# Laser_protection.net
KiCad netlist of a schematic drawn in Altium Designer
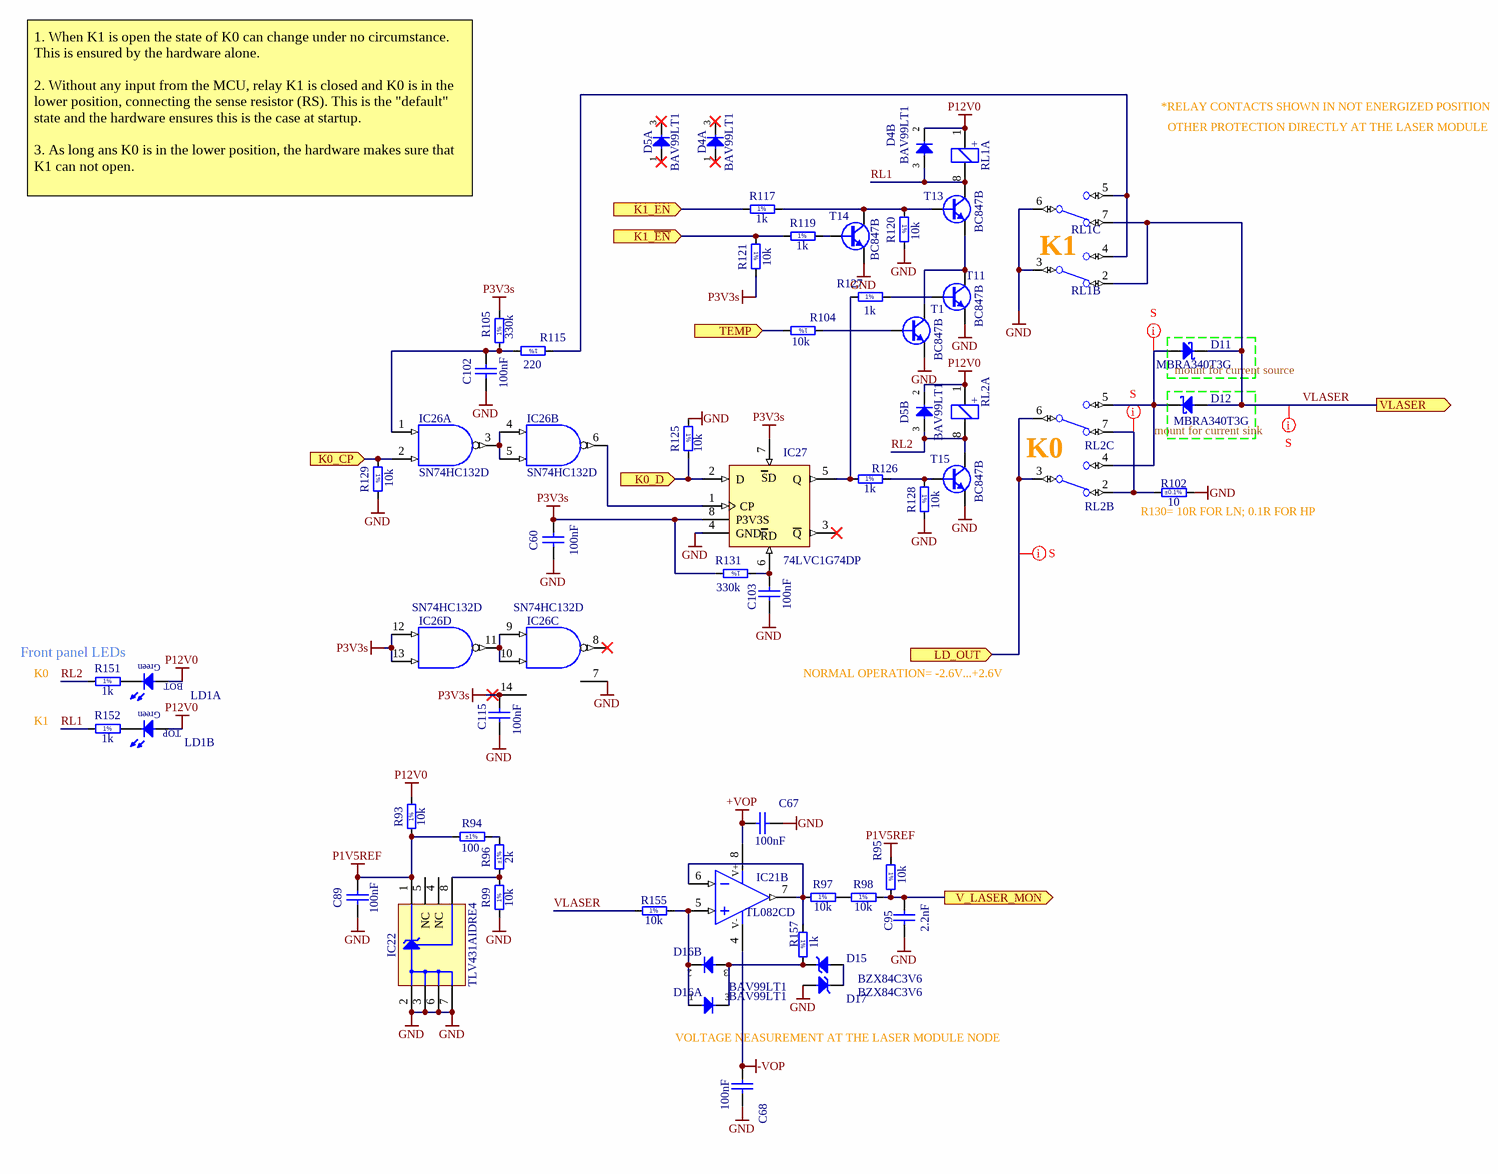
[diagram p0: Laser protection.SchDoc]

(export (version "E")
  (design (tool "Eeschema 10.0.6"))
  (components
    (comp (ref "C60")
      (value "100nF")
      (footprint "CAPC1608X87N")
      (description "Non-polarised capacitor")
      (fields
        (field (name "PART NUMBER") "CC0603_100NF_50V_10%_X7R")
        (field (name "VOLTAGE") "50V")
        (field (name "AUTHOR") "CERN DEM JLC")
      )
      (libsource (lib "Capacitors") (part "Capacitor - non polarized"))
    )
    (comp (ref "C67")
      (value "100nF")
      (footprint "CAPC1608X87N")
      (description "Non-polarised capacitor")
      (fields
        (field (name "PART NUMBER") "CC0603_100NF_50V_10%_X7R")
        (field (name "VOLTAGE") "50V")
        (field (name "AUTHOR") "CERN DEM JLC")
      )
      (libsource (lib "Capacitors") (part "Capacitor - non polarized"))
    )
    (comp (ref "C68")
      (value "100nF")
      (footprint "CAPC1608X87N")
      (description "Non-polarised capacitor")
      (fields
        (field (name "PART NUMBER") "CC0603_100NF_50V_10%_X7R")
        (field (name "VOLTAGE") "50V")
        (field (name "AUTHOR") "CERN DEM JLC")
      )
      (libsource (lib "Capacitors") (part "Capacitor - non polarized"))
    )
    (comp (ref "C89")
      (value "100nF")
      (footprint "CAPC1608X87N")
      (description "Non-polarised capacitor")
      (fields
        (field (name "PART NUMBER") "CC0603_100NF_50V_10%_X7R")
        (field (name "VOLTAGE") "50V")
        (field (name "AUTHOR") "CERN DEM JLC")
      )
      (libsource (lib "Capacitors") (part "Capacitor - non polarized"))
    )
    (comp (ref "C95")
      (value "2.2nF")
      (footprint "CAPC1608X87N")
      (description "Non-polarised capacitor")
      (fields
        (field (name "PART NUMBER") "CC0603_2.2NF_50V_5%_C0G")
        (field (name "VOLTAGE") "50V")
        (field (name "AUTHOR") "CERN DEM JMW")
      )
      (libsource (lib "Capacitors") (part "Capacitor - non polarized"))
    )
    (comp (ref "C102")
      (value "100nF")
      (footprint "CAPC1608X87N")
      (description "Non-polarised capacitor")
      (fields
        (field (name "PART NUMBER") "CC0603_100NF_50V_10%_X7R")
        (field (name "VOLTAGE") "50V")
        (field (name "AUTHOR") "CERN DEM JLC")
      )
      (libsource (lib "Capacitors") (part "Capacitor - non polarized"))
    )
    (comp (ref "C103")
      (value "100nF")
      (footprint "CAPC1608X87N")
      (description "Non-polarised capacitor")
      (fields
        (field (name "PART NUMBER") "CC0603_100NF_50V_10%_X7R")
        (field (name "VOLTAGE") "50V")
        (field (name "AUTHOR") "CERN DEM JLC")
      )
      (libsource (lib "Capacitors") (part "Capacitor - non polarized"))
    )
    (comp (ref "C115")
      (value "100nF")
      (footprint "CAPC1608X87N")
      (description "Non-polarised capacitor")
      (fields
        (field (name "PART NUMBER") "CC0603_100NF_50V_10%_X7R")
        (field (name "VOLTAGE") "50V")
        (field (name "AUTHOR") "CERN DEM JLC")
      )
      (libsource (lib "Capacitors") (part "Capacitor - non polarized"))
    )
    (comp (ref "D4")
      (value "BAV99LT1")
      (footprint "SOT95P240X110-3N")
      (description "Serial Diode")
      (fields
        (field (name "VOLTAGE") "70V")
        (field (name "POWER") "225mW")
        (field (name "AUTHOR") "CERN DEM JLC")
      )
      (libsource (lib "ICs And Semiconductors") (part "Diode x2 A1C3_A3C2"))
    )
    (comp (ref "D5")
      (value "BAV99LT1")
      (footprint "SOT95P240X110-3N")
      (description "Serial Diode")
      (fields
        (field (name "VOLTAGE") "70V")
        (field (name "POWER") "225mW")
        (field (name "AUTHOR") "CERN DEM JLC")
      )
      (libsource (lib "ICs And Semiconductors") (part "Diode x2 A1C3_A3C2"))
    )
    (comp (ref "D11")
      (value "MBRA340T3G")
      (footprint "DIOM5226X220N")
      (description "Schottky Diode")
      (fields
        (field (name "VOLTAGE") "40V")
        (field (name "POWER") "3A")
        (field (name "AUTHOR") "CERN DEM JLC")
      )
      (libsource (lib "ICs And Semiconductors") (part "Diode Schottky"))
    )
    (comp (ref "D12")
      (value "MBRA340T3G")
      (footprint "DIOM5226X220N")
      (description "Schottky Diode")
      (fields
        (field (name "VOLTAGE") "40V")
        (field (name "POWER") "3A")
        (field (name "AUTHOR") "CERN DEM JLC")
      )
      (libsource (lib "ICs And Semiconductors") (part "Diode Schottky"))
    )
    (comp (ref "D15")
      (value "BZX84C3V6")
      (footprint "SOT95P240X130-3N")
      (description "Diode Zener Anode Pin 1 Cathode Pin 3 (Pas de pin 2)")
      (fields
        (field (name "VOLTAGE") "3V6")
        (field (name "POWER") "350mW")
        (field (name "AUTHOR") "CERN DEM JLC")
      )
      (libsource (lib "ICs And Semiconductors") (part "Diode Zener A1C3"))
    )
    (comp (ref "D16")
      (value "BAV99LT1")
      (footprint "SOT95P240X110-3N")
      (description "Serial Diode")
      (fields
        (field (name "VOLTAGE") "70V")
        (field (name "POWER") "225mW")
        (field (name "AUTHOR") "CERN DEM JLC")
      )
      (libsource (lib "ICs And Semiconductors") (part "Diode x2 A1C3_A3C2"))
    )
    (comp (ref "D17")
      (value "BZX84C3V6")
      (footprint "SOT95P240X130-3N")
      (description "Diode Zener Anode Pin 1 Cathode Pin 3 (Pas de pin 2)")
      (fields
        (field (name "VOLTAGE") "3V6")
        (field (name "POWER") "350mW")
        (field (name "AUTHOR") "CERN DEM JLC")
      )
      (libsource (lib "ICs And Semiconductors") (part "Diode Zener A1C3"))
    )
    (comp (ref "IC21")
      (value "TL082CD")
      (footprint "SOIC127P600X175-8N")
      (description "Dual Operational Amplifier")
      (fields (field (name "MANUFACTURER") "TEXAS INSTRUMENTS") (field (name "AUTHOR") "CERN DEM JLC"))
      (libsource (lib "ICs And Semiconductors") (part "Operational Amplifier x2 Type1"))
    )
    (comp (ref "IC22")
      (value "TLV431AIDRE4")
      (footprint "SOIC127P600X175-8N")
      (description "Precision Programmable Reference")
      (fields (field (name "MANUFACTURER") "TEXAS INSTRUMENTS") (field (name "AUTHOR") "CERN DEM JLC"))
      (libsource (lib "ICs And Semiconductors") (part "TL431xD"))
    )
    (comp (ref "IC26")
      (value "SN74HC132D")
      (footprint "SOIC127P600X175-14N")
      (description "Quad Positive NAND Gate With Schmitt-Trigger Input")
      (fields (field (name "MANUFACTURER") "TEXAS INSTRUMENTS") (field (name "AUTHOR") "CERN DEM JLC"))
      (libsource (lib "") (part "74132_1"))
    )
    (comp (ref "IC27")
      (value "74LVC1G74DP")
      (footprint "SOP65P400X110-8N")
      (description "Single D-type flip-flop with set and reset, positive edge trigger")
      (fields (field (name "MANUFACTURER") "NXP SEMICONDUCTORS") (field (name "AUTHOR") "CERN DEM JLC"))
      (libsource (lib "ICs And Semiconductors") (part "741G74"))
    )
    (comp (ref "LD1")
      (value "Green/Green")
      (footprint "LED_DIALIGHT_571-0122F")
      (description "LED x2 Green 1C2A-BOT_3C4A-TOP")
      (fields
        (field (name "PART NUMBER") "LED_DIALIGHT_571-0122F")
        (field (name "MANUFACTURER") "DIALIGHT")
        (field (name "AUTHOR") "CERN DEM JLC")
      )
      (libsource (lib "ICs And Semiconductors") (part "LED x2 Green 1C2A-BOT_3C4A-TOP"))
    )
    (comp (ref "R93")
      (value "10k")
      (footprint "RESC1608X55N")
      (description "Resistor - 1%")
      (fields
        (field (name "PART NUMBER") "R0603_10K_1%_0.1W_100PPM")
        (field (name "POWER") "0.1W")
        (field (name "AUTHOR") "CERN DEM JLC")
      )
      (libsource (lib "Resistors") (part "Resistor - 1%"))
    )
    (comp (ref "R94")
      (value "100")
      (footprint "RESC1608X55N")
      (description "Resistor - 1%")
      (fields
        (field (name "TOLERANCE") "±1%")
        (field (name "PART NUMBER") "R0603_100R_1%_0.1W_100PPM")
        (field (name "POWER") "0.1W")
        (field (name "AUTHOR") "CERN DEM JLC")
      )
      (libsource (lib "Resistors") (part "Resistor - 1%"))
    )
    (comp (ref "R95")
      (value "10k")
      (footprint "RESC1608X55N")
      (description "Resistor - 1%")
      (fields
        (field (name "PART NUMBER") "R0603_10K_1%_0.1W_100PPM")
        (field (name "POWER") "0.1W")
        (field (name "AUTHOR") "CERN DEM JLC")
      )
      (libsource (lib "Resistors") (part "Resistor - 1%"))
    )
    (comp (ref "R96")
      (value "2k")
      (footprint "RESC1608X55N")
      (description "Resistor - 1%")
      (fields
        (field (name "TOLERANCE") "±1%")
        (field (name "PART NUMBER") "R0603_2K_1%_0.1W_100PPM")
        (field (name "POWER") "0.1W")
        (field (name "AUTHOR") "CERN DEM JLC")
      )
      (libsource (lib "Resistors") (part "Resistor - 1%"))
    )
    (comp (ref "R97")
      (value "10k")
      (footprint "RESC1608X55N")
      (description "Resistor - 1%")
      (fields
        (field (name "PART NUMBER") "R0603_10K_1%_0.1W_100PPM")
        (field (name "POWER") "0.1W")
        (field (name "AUTHOR") "CERN DEM JLC")
      )
      (libsource (lib "Resistors") (part "Resistor - 1%"))
    )
    (comp (ref "R98")
      (value "10k")
      (footprint "RESC1608X55N")
      (description "Resistor - 1%")
      (fields
        (field (name "PART NUMBER") "R0603_10K_1%_0.1W_100PPM")
        (field (name "POWER") "0.1W")
        (field (name "AUTHOR") "CERN DEM JLC")
      )
      (libsource (lib "Resistors") (part "Resistor - 1%"))
    )
    (comp (ref "R99")
      (value "10k")
      (footprint "RESC1608X55N")
      (description "Resistor - 1%")
      (fields
        (field (name "PART NUMBER") "R0603_10K_1%_0.1W_100PPM")
        (field (name "POWER") "0.1W")
        (field (name "AUTHOR") "CERN DEM JLC")
      )
      (libsource (lib "Resistors") (part "Resistor - 1%"))
    )
    (comp (ref "R102")
      (value "10")
      (footprint "RESC6531X85N")
      (description "Resistor - 0.1%")
      (fields
        (field (name "TOLERANCE") "±0.1%")
        (field (name "PART NUMBER") "R2512_10R_0.1%_2.5W_25PPM")
        (field (name "POWER") "2.5W")
        (field (name "AUTHOR") "CERN DEM JLC")
      )
      (libsource (lib "Resistors") (part "Resistor - 0.1%"))
    )
    (comp (ref "R104")
      (value "10k")
      (footprint "RESC1608X55N")
      (description "Resistor - 1%")
      (fields
        (field (name "PART NUMBER") "R0603_10K_1%_0.1W_100PPM")
        (field (name "POWER") "0.1W")
        (field (name "AUTHOR") "CERN DEM JLC")
      )
      (libsource (lib "Resistors") (part "Resistor - 1%"))
    )
    (comp (ref "R105")
      (value "330k")
      (footprint "RESC1608X55N")
      (description "Resistor - 1%")
      (fields
        (field (name "PART NUMBER") "R0603_330K_1%_0.1W_100PPM")
        (field (name "POWER") "0.1W")
        (field (name "AUTHOR") "CERN DEM JLC")
      )
      (libsource (lib "Resistors") (part "Resistor - 1%"))
    )
    (comp (ref "R115")
      (value "220")
      (footprint "RESC1608X55N")
      (description "Resistor - 1%")
      (fields
        (field (name "PART NUMBER") "R0603_220R_1%_0.1W_100PPM")
        (field (name "POWER") "0.1W")
        (field (name "AUTHOR") "CERN DEM JLC")
      )
      (libsource (lib "Resistors") (part "Resistor - 1%"))
    )
    (comp (ref "R117")
      (value "1k")
      (footprint "RESC1608X55N")
      (description "Resistor - 1%")
      (fields
        (field (name "PART NUMBER") "R0603_1K_1%_0.1W_100PPM")
        (field (name "POWER") "0.1W")
        (field (name "AUTHOR") "CERN DEM JLC")
      )
      (libsource (lib "Resistors") (part "Resistor - 1%"))
    )
    (comp (ref "R119")
      (value "1k")
      (footprint "RESC1608X55N")
      (description "Resistor - 1%")
      (fields
        (field (name "PART NUMBER") "R0603_1K_1%_0.1W_100PPM")
        (field (name "POWER") "0.1W")
        (field (name "AUTHOR") "CERN DEM JLC")
      )
      (libsource (lib "Resistors") (part "Resistor - 1%"))
    )
    (comp (ref "R120")
      (value "10k")
      (footprint "RESC1608X55N")
      (description "Resistor - 1%")
      (fields
        (field (name "PART NUMBER") "R0603_10K_1%_0.1W_100PPM")
        (field (name "POWER") "0.1W")
        (field (name "AUTHOR") "CERN DEM JLC")
      )
      (libsource (lib "Resistors") (part "Resistor - 1%"))
    )
    (comp (ref "R121")
      (value "10k")
      (footprint "RESC1608X55N")
      (description "Resistor - 1%")
      (fields
        (field (name "PART NUMBER") "R0603_10K_1%_0.1W_100PPM")
        (field (name "POWER") "0.1W")
        (field (name "AUTHOR") "CERN DEM JLC")
      )
      (libsource (lib "Resistors") (part "Resistor - 1%"))
    )
    (comp (ref "R125")
      (value "10k")
      (footprint "RESC1608X55N")
      (description "Resistor - 1%")
      (fields
        (field (name "PART NUMBER") "R0603_10K_1%_0.1W_100PPM")
        (field (name "POWER") "0.1W")
        (field (name "AUTHOR") "CERN DEM JLC")
      )
      (libsource (lib "Resistors") (part "Resistor - 1%"))
    )
    (comp (ref "R126")
      (value "1k")
      (footprint "RESC1608X55N")
      (description "Resistor - 1%")
      (fields
        (field (name "PART NUMBER") "R0603_1K_1%_0.1W_100PPM")
        (field (name "POWER") "0.1W")
        (field (name "AUTHOR") "CERN DEM JLC")
      )
      (libsource (lib "Resistors") (part "Resistor - 1%"))
    )
    (comp (ref "R127")
      (value "1k")
      (footprint "RESC1608X55N")
      (description "Resistor - 1%")
      (fields
        (field (name "PART NUMBER") "R0603_1K_1%_0.1W_100PPM")
        (field (name "POWER") "0.1W")
        (field (name "AUTHOR") "CERN DEM JLC")
      )
      (libsource (lib "Resistors") (part "Resistor - 1%"))
    )
    (comp (ref "R128")
      (value "10k")
      (footprint "RESC1608X55N")
      (description "Resistor - 1%")
      (fields
        (field (name "PART NUMBER") "R0603_10K_1%_0.1W_100PPM")
        (field (name "POWER") "0.1W")
        (field (name "AUTHOR") "CERN DEM JLC")
      )
      (libsource (lib "Resistors") (part "Resistor - 1%"))
    )
    (comp (ref "R129")
      (value "10k")
      (footprint "RESC1608X55N")
      (description "Resistor - 1%")
      (fields
        (field (name "PART NUMBER") "R0603_10K_1%_0.1W_100PPM")
        (field (name "POWER") "0.1W")
        (field (name "AUTHOR") "CERN DEM JLC")
      )
      (libsource (lib "Resistors") (part "Resistor - 1%"))
    )
    (comp (ref "R131")
      (value "330k")
      (footprint "RESC1608X55N")
      (description "Resistor - 1%")
      (fields
        (field (name "PART NUMBER") "R0603_330K_1%_0.1W_100PPM")
        (field (name "POWER") "0.1W")
        (field (name "AUTHOR") "CERN DEM JLC")
      )
      (libsource (lib "Resistors") (part "Resistor - 1%"))
    )
    (comp (ref "R151")
      (value "1k")
      (footprint "RESC1608X55N")
      (description "Resistor - 1%")
      (fields
        (field (name "PART NUMBER") "R0603_1K_1%_0.1W_100PPM")
        (field (name "POWER") "0.1W")
        (field (name "AUTHOR") "CERN DEM JLC")
      )
      (libsource (lib "Resistors") (part "Resistor - 1%"))
    )
    (comp (ref "R152")
      (value "1k")
      (footprint "RESC1608X55N")
      (description "Resistor - 1%")
      (fields
        (field (name "PART NUMBER") "R0603_1K_1%_0.1W_100PPM")
        (field (name "POWER") "0.1W")
        (field (name "AUTHOR") "CERN DEM JLC")
      )
      (libsource (lib "Resistors") (part "Resistor - 1%"))
    )
    (comp (ref "R155")
      (value "10k")
      (footprint "RESC1608X55N")
      (description "Resistor - 1%")
      (fields
        (field (name "PART NUMBER") "R0603_10K_1%_0.1W_100PPM")
        (field (name "POWER") "0.1W")
        (field (name "AUTHOR") "CERN DEM JLC")
      )
      (libsource (lib "Resistors") (part "Resistor - 1%"))
    )
    (comp (ref "R157")
      (value "1k")
      (footprint "RESC1608X55N")
      (description "Resistor - 1%")
      (fields
        (field (name "PART NUMBER") "R0603_1K_1%_0.1W_100PPM")
        (field (name "POWER") "0.1W")
        (field (name "AUTHOR") "CERN DEM JLC")
      )
      (libsource (lib "Resistors") (part "Resistor - 1%"))
    )
    (comp (ref "RL1")
      (value "REL_TYCO_IM Non-latching")
      (footprint "REL_TYCO_IMXXXGX")
      (description "IM Signal Relay (Monostable 1 Coil Non-latching)")
      (fields
        (field (name "PART NUMBER") "REL_TYCO_IM06CGR")
        (field (name "MANUFACTURER") "TYCO AXICOM")
        (field (name "AUTHOR") "CERN DEM JLC")
      )
      (libsource (lib "Eletro-mechanical") (part "REL_TYCO_IM Non-latching"))
    )
    (comp (ref "RL2")
      (value "REL_TYCO_IM Non-latching")
      (footprint "REL_TYCO_IMXXXGX")
      (description "IM Signal Relay (Monostable 1 Coil Non-latching)")
      (fields
        (field (name "PART NUMBER") "REL_TYCO_IM06CGR")
        (field (name "MANUFACTURER") "TYCO AXICOM")
        (field (name "AUTHOR") "CERN DEM JLC")
      )
      (libsource (lib "Eletro-mechanical") (part "REL_TYCO_IM Non-latching"))
    )
    (comp (ref "T1")
      (value "BC847B")
      (footprint "SOT95P230X110-3N")
      (description "NPN Transistor")
      (fields (field (name "MANUFACTURER") "NXP SEMICONDUCTORS") (field (name "AUTHOR") "CERN DEM JLC"))
      (libsource (lib "ICs And Semiconductors") (part "NPN B1 E2 C3"))
    )
    (comp (ref "T11")
      (value "BC847B")
      (footprint "SOT95P230X110-3N")
      (description "NPN Transistor")
      (fields (field (name "MANUFACTURER") "NXP SEMICONDUCTORS") (field (name "AUTHOR") "CERN DEM JLC"))
      (libsource (lib "ICs And Semiconductors") (part "NPN B1 E2 C3"))
    )
    (comp (ref "T13")
      (value "BC847B")
      (footprint "SOT95P230X110-3N")
      (description "NPN Transistor")
      (fields (field (name "MANUFACTURER") "NXP SEMICONDUCTORS") (field (name "AUTHOR") "CERN DEM JLC"))
      (libsource (lib "ICs And Semiconductors") (part "NPN B1 E2 C3"))
    )
    (comp (ref "T14")
      (value "BC847B")
      (footprint "SOT95P230X110-3N")
      (description "NPN Transistor")
      (fields (field (name "MANUFACTURER") "NXP SEMICONDUCTORS") (field (name "AUTHOR") "CERN DEM JLC"))
      (libsource (lib "ICs And Semiconductors") (part "NPN B1 E2 C3"))
    )
    (comp (ref "T15")
      (value "BC847B")
      (footprint "SOT95P230X110-3N")
      (description "NPN Transistor")
      (fields (field (name "MANUFACTURER") "NXP SEMICONDUCTORS") (field (name "AUTHOR") "CERN DEM JLC"))
      (libsource (lib "ICs And Semiconductors") (part "NPN B1 E2 C3"))
    )
  )
  (nets
    (net (code "1") (name "+VOP") (class "Default")
      (node (ref "C67") (pin "1") (pinfunction "1_1") (pintype "passive"))
      (node (ref "IC21") (pin "8") (pinfunction "V+_8") (pintype "power_in"))
    )
    (net (code "2") (name "-VOP") (class "Default")
      (node (ref "C68") (pin "1") (pinfunction "1_1") (pintype "passive"))
      (node (ref "IC21") (pin "4") (pinfunction "V-_4") (pintype "power_in"))
    )
    (net (code "3") (name "/K0_CP") (class "Default")
      (node (ref "IC26") (pin "2") (pinfunction "B_2") (pintype "input"))
      (node (ref "R129") (pin "1") (pinfunction "1_1") (pintype "passive"))
    )
    (net (code "4") (name "/K0_D") (class "Default")
      (node (ref "IC27") (pin "2") (pinfunction "D_2") (pintype "input"))
      (node (ref "R125") (pin "2") (pinfunction "2_2") (pintype "passive"))
    )
    (net (code "5") (name "/K1_EN") (class "Default")
      (node (ref "R117") (pin "1") (pinfunction "1_1") (pintype "passive"))
    )
    (net (code "6") (name "/K1_~{EN}") (class "Default")
      (node (ref "R119") (pin "1") (pinfunction "1_1") (pintype "passive"))
      (node (ref "R121") (pin "1") (pinfunction "1_1") (pintype "passive"))
    )
    (net (code "7") (name "/LD_OUT") (class "Default")
      (node (ref "RL2") (pin "3") (pinfunction "C_3") (pintype "bidirectional"))
      (node (ref "RL2") (pin "6") (pinfunction "C_6") (pintype "bidirectional"))
    )
    (net (code "8") (name "/RL1") (class "Default")
      (node (ref "D4") (pin "3") (pinfunction "COMAC_3") (pintype "passive"))
      (node (ref "R152") (pin "1") (pinfunction "1_1") (pintype "passive"))
      (node (ref "RL1") (pin "8") (pinfunction "8_8") (pintype "passive"))
      (node (ref "T13") (pin "3") (pinfunction "C_3") (pintype "passive"))
    )
    (net (code "9") (name "/RL2") (class "Default")
      (node (ref "D5") (pin "3") (pinfunction "COMAC_3") (pintype "passive"))
      (node (ref "R151") (pin "1") (pinfunction "1_1") (pintype "passive"))
      (node (ref "RL2") (pin "8") (pinfunction "8_8") (pintype "passive"))
      (node (ref "T15") (pin "3") (pinfunction "C_3") (pintype "passive"))
    )
    (net (code "10") (name "/TEMP") (class "Default")
      (node (ref "R104") (pin "2") (pinfunction "2_2") (pintype "passive"))
    )
    (net (code "11") (name "/VLASER") (class "Default")
      (node (ref "D11") (pin "1") (pinfunction "C_1") (pintype "passive"))
      (node (ref "D12") (pin "2") (pinfunction "A_2") (pintype "passive"))
      (node (ref "R155") (pin "1") (pinfunction "1_1") (pintype "passive"))
      (node (ref "RL1") (pin "2") (pinfunction "NC_2") (pintype "bidirectional"))
      (node (ref "RL1") (pin "7") (pinfunction "NC_7") (pintype "bidirectional"))
    )
    (net (code "12") (name "/V_LASER_MON") (class "Default")
      (node (ref "C95") (pin "2") (pinfunction "2_2") (pintype "passive"))
      (node (ref "R95") (pin "2") (pinfunction "2_2") (pintype "passive"))
      (node (ref "R98") (pin "2") (pinfunction "2_2") (pintype "passive"))
    )
    (net (code "13") (name "GND") (class "Default")
      (node (ref "C102") (pin "1") (pinfunction "1_1") (pintype "passive"))
      (node (ref "C103") (pin "1") (pinfunction "1_1") (pintype "passive"))
      (node (ref "C115") (pin "1") (pinfunction "1_1") (pintype "passive"))
      (node (ref "C60") (pin "1") (pinfunction "1_1") (pintype "passive"))
      (node (ref "C67") (pin "2") (pinfunction "2_2") (pintype "passive"))
      (node (ref "C68") (pin "2") (pinfunction "2_2") (pintype "passive"))
      (node (ref "C89") (pin "1") (pinfunction "1_1") (pintype "passive"))
      (node (ref "C95") (pin "1") (pinfunction "1_1") (pintype "passive"))
      (node (ref "D17") (pin "1") (pinfunction "A_1") (pintype "passive"))
      (node (ref "IC22") (pin "2") (pinfunction "A_2") (pintype "passive"))
      (node (ref "IC22") (pin "3") (pinfunction "A_3") (pintype "passive"))
      (node (ref "IC22") (pin "6") (pinfunction "A_6") (pintype "passive"))
      (node (ref "IC22") (pin "7") (pinfunction "A_7") (pintype "passive"))
      (node (ref "IC26") (pin "7") (pinfunction "GND_7") (pintype "power_in"))
      (node (ref "IC27") (pin "4") (pinfunction "GND_4") (pintype "power_in"))
      (node (ref "R102") (pin "2") (pinfunction "2_2") (pintype "passive"))
      (node (ref "R120") (pin "2") (pinfunction "2_2") (pintype "passive"))
      (node (ref "R125") (pin "1") (pinfunction "1_1") (pintype "passive"))
      (node (ref "R128") (pin "2") (pinfunction "2_2") (pintype "passive"))
      (node (ref "R129") (pin "2") (pinfunction "2_2") (pintype "passive"))
      (node (ref "R99") (pin "1") (pinfunction "1_1") (pintype "passive"))
      (node (ref "RL1") (pin "3") (pinfunction "C_3") (pintype "bidirectional"))
      (node (ref "RL1") (pin "6") (pinfunction "C_6") (pintype "bidirectional"))
      (node (ref "T1") (pin "2") (pinfunction "E_2") (pintype "passive"))
      (node (ref "T11") (pin "2") (pinfunction "E_2") (pintype "passive"))
      (node (ref "T14") (pin "2") (pinfunction "E_2") (pintype "passive"))
      (node (ref "T15") (pin "2") (pinfunction "E_2") (pintype "passive"))
    )
    (net (code "14") (name "Net-(D11-A)") (class "Default")
      (node (ref "D11") (pin "2") (pinfunction "A_2") (pintype "passive"))
      (node (ref "D12") (pin "1") (pinfunction "C_1") (pintype "passive"))
      (node (ref "RL2") (pin "4") (pinfunction "NO_4") (pintype "bidirectional"))
      (node (ref "RL2") (pin "5") (pinfunction "NO_5") (pintype "bidirectional"))
    )
    (net (code "15") (name "Net-(D15-A)") (class "Default")
      (node (ref "D15") (pin "1") (pinfunction "A_1") (pintype "passive"))
      (node (ref "D17") (pin "3") (pinfunction "C_3") (pintype "passive"))
    )
    (net (code "16") (name "Net-(D15-C)") (class "Default")
      (node (ref "D15") (pin "3") (pinfunction "C_3") (pintype "passive"))
      (node (ref "D16") (pin "3") (pinfunction "COMAC_3") (pintype "passive"))
      (node (ref "R157") (pin "2") (pinfunction "2_2") (pintype "passive"))
    )
    (net (code "17") (name "Net-(D16A-A)") (class "Default")
      (node (ref "D16") (pin "1") (pinfunction "A_1") (pintype "passive"))
      (node (ref "D16") (pin "2") (pinfunction "C_2") (pintype "passive"))
      (node (ref "IC21") (pin "5") (pinfunction "IN+_5") (pintype "input"))
      (node (ref "R155") (pin "2") (pinfunction "2_2") (pintype "passive"))
    )
    (net (code "18") (name "Net-(IC21B-IN-)") (class "Default")
      (node (ref "IC21") (pin "6") (pinfunction "IN-_6") (pintype "input"))
      (node (ref "IC21") (pin "7") (pinfunction "OUT_7") (pintype "output"))
      (node (ref "R157") (pin "1") (pinfunction "1_1") (pintype "passive"))
      (node (ref "R97") (pin "1") (pinfunction "1_1") (pintype "passive"))
    )
    (net (code "19") (name "Net-(IC22-REF)") (class "Default")
      (node (ref "IC22") (pin "8") (pinfunction "REF_8") (pintype "passive"))
      (node (ref "R96") (pin "1") (pinfunction "1_1") (pintype "passive"))
      (node (ref "R99") (pin "2") (pinfunction "2_2") (pintype "passive"))
    )
    (net (code "20") (name "Net-(IC26A-A)") (class "Default")
      (node (ref "C102") (pin "2") (pinfunction "2_2") (pintype "passive"))
      (node (ref "IC26") (pin "1") (pinfunction "A_1") (pintype "input"))
      (node (ref "R105") (pin "1") (pinfunction "1_1") (pintype "passive"))
      (node (ref "R115") (pin "2") (pinfunction "2_2") (pintype "passive"))
    )
    (net (code "21") (name "Net-(IC26A-~{O})") (class "Default")
      (node (ref "IC26") (pin "3") (pinfunction "~{O}_3") (pintype "output"))
      (node (ref "IC26") (pin "4") (pinfunction "A_4") (pintype "input"))
      (node (ref "IC26") (pin "5") (pinfunction "B_5") (pintype "input"))
    )
    (net (code "22") (name "Net-(IC26B-~{O})") (class "Default")
      (node (ref "IC26") (pin "6") (pinfunction "~{O}_6") (pintype "output"))
      (node (ref "IC27") (pin "1") (pinfunction "CP_1") (pintype "input"))
    )
    (net (code "23") (name "Net-(IC26C-A)") (class "Default")
      (node (ref "IC26") (pin "10") (pinfunction "B_10") (pintype "input"))
      (node (ref "IC26") (pin "11") (pinfunction "~{O}_11") (pintype "output"))
      (node (ref "IC26") (pin "9") (pinfunction "A_9") (pintype "input"))
    )
    (net (code "24") (name "Net-(IC27-Q)") (class "Default")
      (node (ref "IC27") (pin "5") (pinfunction "Q_5") (pintype "output"))
      (node (ref "R126") (pin "1") (pinfunction "1_1") (pintype "passive"))
      (node (ref "R127") (pin "1") (pinfunction "1_1") (pintype "passive"))
    )
    (net (code "25") (name "Net-(IC27-~{RD})") (class "Default")
      (node (ref "C103") (pin "2") (pinfunction "2_2") (pintype "passive"))
      (node (ref "IC27") (pin "6") (pinfunction "~{RD}_6") (pintype "input"))
      (node (ref "R131") (pin "1") (pinfunction "1_1") (pintype "passive"))
    )
    (net (code "26") (name "Net-(LD1A-C)") (class "Default")
      (node (ref "LD1") (pin "1") (pinfunction "C_1") (pintype "passive"))
      (node (ref "R151") (pin "2") (pinfunction "2_2") (pintype "passive"))
    )
    (net (code "27") (name "Net-(LD1B-C)") (class "Default")
      (node (ref "LD1") (pin "3") (pinfunction "C_3") (pintype "passive"))
      (node (ref "R152") (pin "2") (pinfunction "2_2") (pintype "passive"))
    )
    (net (code "28") (name "Net-(R94-Pad1)") (class "Default")
      (node (ref "R94") (pin "1") (pinfunction "1_1") (pintype "passive"))
      (node (ref "R96") (pin "2") (pinfunction "2_2") (pintype "passive"))
    )
    (net (code "29") (name "Net-(R97-Pad2)") (class "Default")
      (node (ref "R97") (pin "2") (pinfunction "2_2") (pintype "passive"))
      (node (ref "R98") (pin "1") (pinfunction "1_1") (pintype "passive"))
    )
    (net (code "30") (name "Net-(RL1B-NO)") (class "Default")
      (node (ref "R115") (pin "1") (pinfunction "1_1") (pintype "passive"))
      (node (ref "RL1") (pin "4") (pinfunction "NO_4") (pintype "bidirectional"))
      (node (ref "RL1") (pin "5") (pinfunction "NO_5") (pintype "bidirectional"))
    )
    (net (code "31") (name "Net-(RL2B-NC)") (class "Default")
      (node (ref "R102") (pin "1") (pinfunction "1_1") (pintype "passive"))
      (node (ref "RL2") (pin "2") (pinfunction "NC_2") (pintype "bidirectional"))
      (node (ref "RL2") (pin "7") (pinfunction "NC_7") (pintype "bidirectional"))
    )
    (net (code "32") (name "Net-(T1-B)") (class "Default")
      (node (ref "R104") (pin "1") (pinfunction "1_1") (pintype "passive"))
      (node (ref "T1") (pin "1") (pinfunction "B_1") (pintype "passive"))
    )
    (net (code "33") (name "Net-(T1-C)") (class "Default")
      (node (ref "T1") (pin "3") (pinfunction "C_3") (pintype "passive"))
      (node (ref "T11") (pin "3") (pinfunction "C_3") (pintype "passive"))
      (node (ref "T13") (pin "2") (pinfunction "E_2") (pintype "passive"))
    )
    (net (code "34") (name "Net-(T11-B)") (class "Default")
      (node (ref "R127") (pin "2") (pinfunction "2_2") (pintype "passive"))
      (node (ref "T11") (pin "1") (pinfunction "B_1") (pintype "passive"))
    )
    (net (code "35") (name "Net-(T13-B)") (class "Default")
      (node (ref "R117") (pin "2") (pinfunction "2_2") (pintype "passive"))
      (node (ref "R120") (pin "1") (pinfunction "1_1") (pintype "passive"))
      (node (ref "T13") (pin "1") (pinfunction "B_1") (pintype "passive"))
      (node (ref "T14") (pin "3") (pinfunction "C_3") (pintype "passive"))
    )
    (net (code "36") (name "Net-(T14-B)") (class "Default")
      (node (ref "R119") (pin "2") (pinfunction "2_2") (pintype "passive"))
      (node (ref "T14") (pin "1") (pinfunction "B_1") (pintype "passive"))
    )
    (net (code "37") (name "Net-(T15-B)") (class "Default")
      (node (ref "R126") (pin "2") (pinfunction "2_2") (pintype "passive"))
      (node (ref "R128") (pin "1") (pinfunction "1_1") (pintype "passive"))
      (node (ref "T15") (pin "1") (pinfunction "B_1") (pintype "passive"))
    )
    (net (code "38") (name "P1V5REF") (class "Default")
      (node (ref "C89") (pin "2") (pinfunction "2_2") (pintype "passive"))
      (node (ref "IC22") (pin "1") (pinfunction "C_1") (pintype "passive"))
      (node (ref "R93") (pin "1") (pinfunction "1_1") (pintype "passive"))
      (node (ref "R94") (pin "2") (pinfunction "2_2") (pintype "passive"))
      (node (ref "R95") (pin "1") (pinfunction "1_1") (pintype "passive"))
    )
    (net (code "39") (name "P3V3s") (class "Default")
      (node (ref "C115") (pin "2") (pinfunction "2_2") (pintype "passive"))
      (node (ref "C60") (pin "2") (pinfunction "2_2") (pintype "passive"))
      (node (ref "IC26") (pin "12") (pinfunction "A_12") (pintype "input"))
      (node (ref "IC26") (pin "13") (pinfunction "B_13") (pintype "input"))
      (node (ref "IC26") (pin "14") (pinfunction "P3V3s_14") (pintype "power_in"))
      (node (ref "IC27") (pin "7") (pinfunction "~{S}D_7") (pintype "input"))
      (node (ref "IC27") (pin "8") (pinfunction "P3V3S_8") (pintype "power_in"))
      (node (ref "R105") (pin "2") (pinfunction "2_2") (pintype "passive"))
      (node (ref "R121") (pin "2") (pinfunction "2_2") (pintype "passive"))
      (node (ref "R131") (pin "2") (pinfunction "2_2") (pintype "passive"))
    )
    (net (code "40") (name "P12V0") (class "Default")
      (node (ref "D4") (pin "2") (pinfunction "C_2") (pintype "passive"))
      (node (ref "D5") (pin "2") (pinfunction "C_2") (pintype "passive"))
      (node (ref "LD1") (pin "2") (pinfunction "A_2") (pintype "passive"))
      (node (ref "LD1") (pin "4") (pinfunction "A_4") (pintype "passive"))
      (node (ref "R93") (pin "2") (pinfunction "2_2") (pintype "passive"))
      (node (ref "RL1") (pin "1") (pinfunction "1_1") (pintype "passive"))
      (node (ref "RL2") (pin "1") (pinfunction "1_1") (pintype "passive"))
    )
    (net (code "41") (name "VCC") (class "Default")
      (node (ref "IC26") (pin "14") (pinfunction "VCC_14") (pintype "power_in"))
    )
    (net (code "42") (name "unconnected-(D4A-A-Pad1)") (class "Default")
      (node (ref "D4") (pin "1") (pinfunction "A_1") (pintype "passive+no_connect"))
    )
    (net (code "43") (name "unconnected-(D4A-COMAC-Pad3)") (class "Default")
      (node (ref "D4") (pin "3") (pinfunction "COMAC_3") (pintype "passive+no_connect"))
    )
    (net (code "44") (name "unconnected-(D5A-A-Pad1)") (class "Default")
      (node (ref "D5") (pin "1") (pinfunction "A_1") (pintype "passive+no_connect"))
    )
    (net (code "45") (name "unconnected-(D5A-COMAC-Pad3)") (class "Default")
      (node (ref "D5") (pin "3") (pinfunction "COMAC_3") (pintype "passive+no_connect"))
    )
    (net (code "46") (name "unconnected-(IC22-NC-Pad4)") (class "Default")
      (node (ref "IC22") (pin "4") (pinfunction "NC_4") (pintype "passive"))
    )
    (net (code "47") (name "unconnected-(IC22-NC-Pad5)") (class "Default")
      (node (ref "IC22") (pin "5") (pinfunction "NC_5") (pintype "passive"))
    )
    (net (code "48") (name "unconnected-(IC26C-~{O}-Pad8)") (class "Default")
      (node (ref "IC26") (pin "8") (pinfunction "~{O}_8") (pintype "output+no_connect"))
    )
    (net (code "49") (name "unconnected-(IC27-~{Q}-Pad3)") (class "Default")
      (node (ref "IC27") (pin "3") (pinfunction "~{Q}_3") (pintype "output+no_connect"))
    )
  )
)
